# sensors.net
KiCad netlist of a schematic drawn in Altium Designer
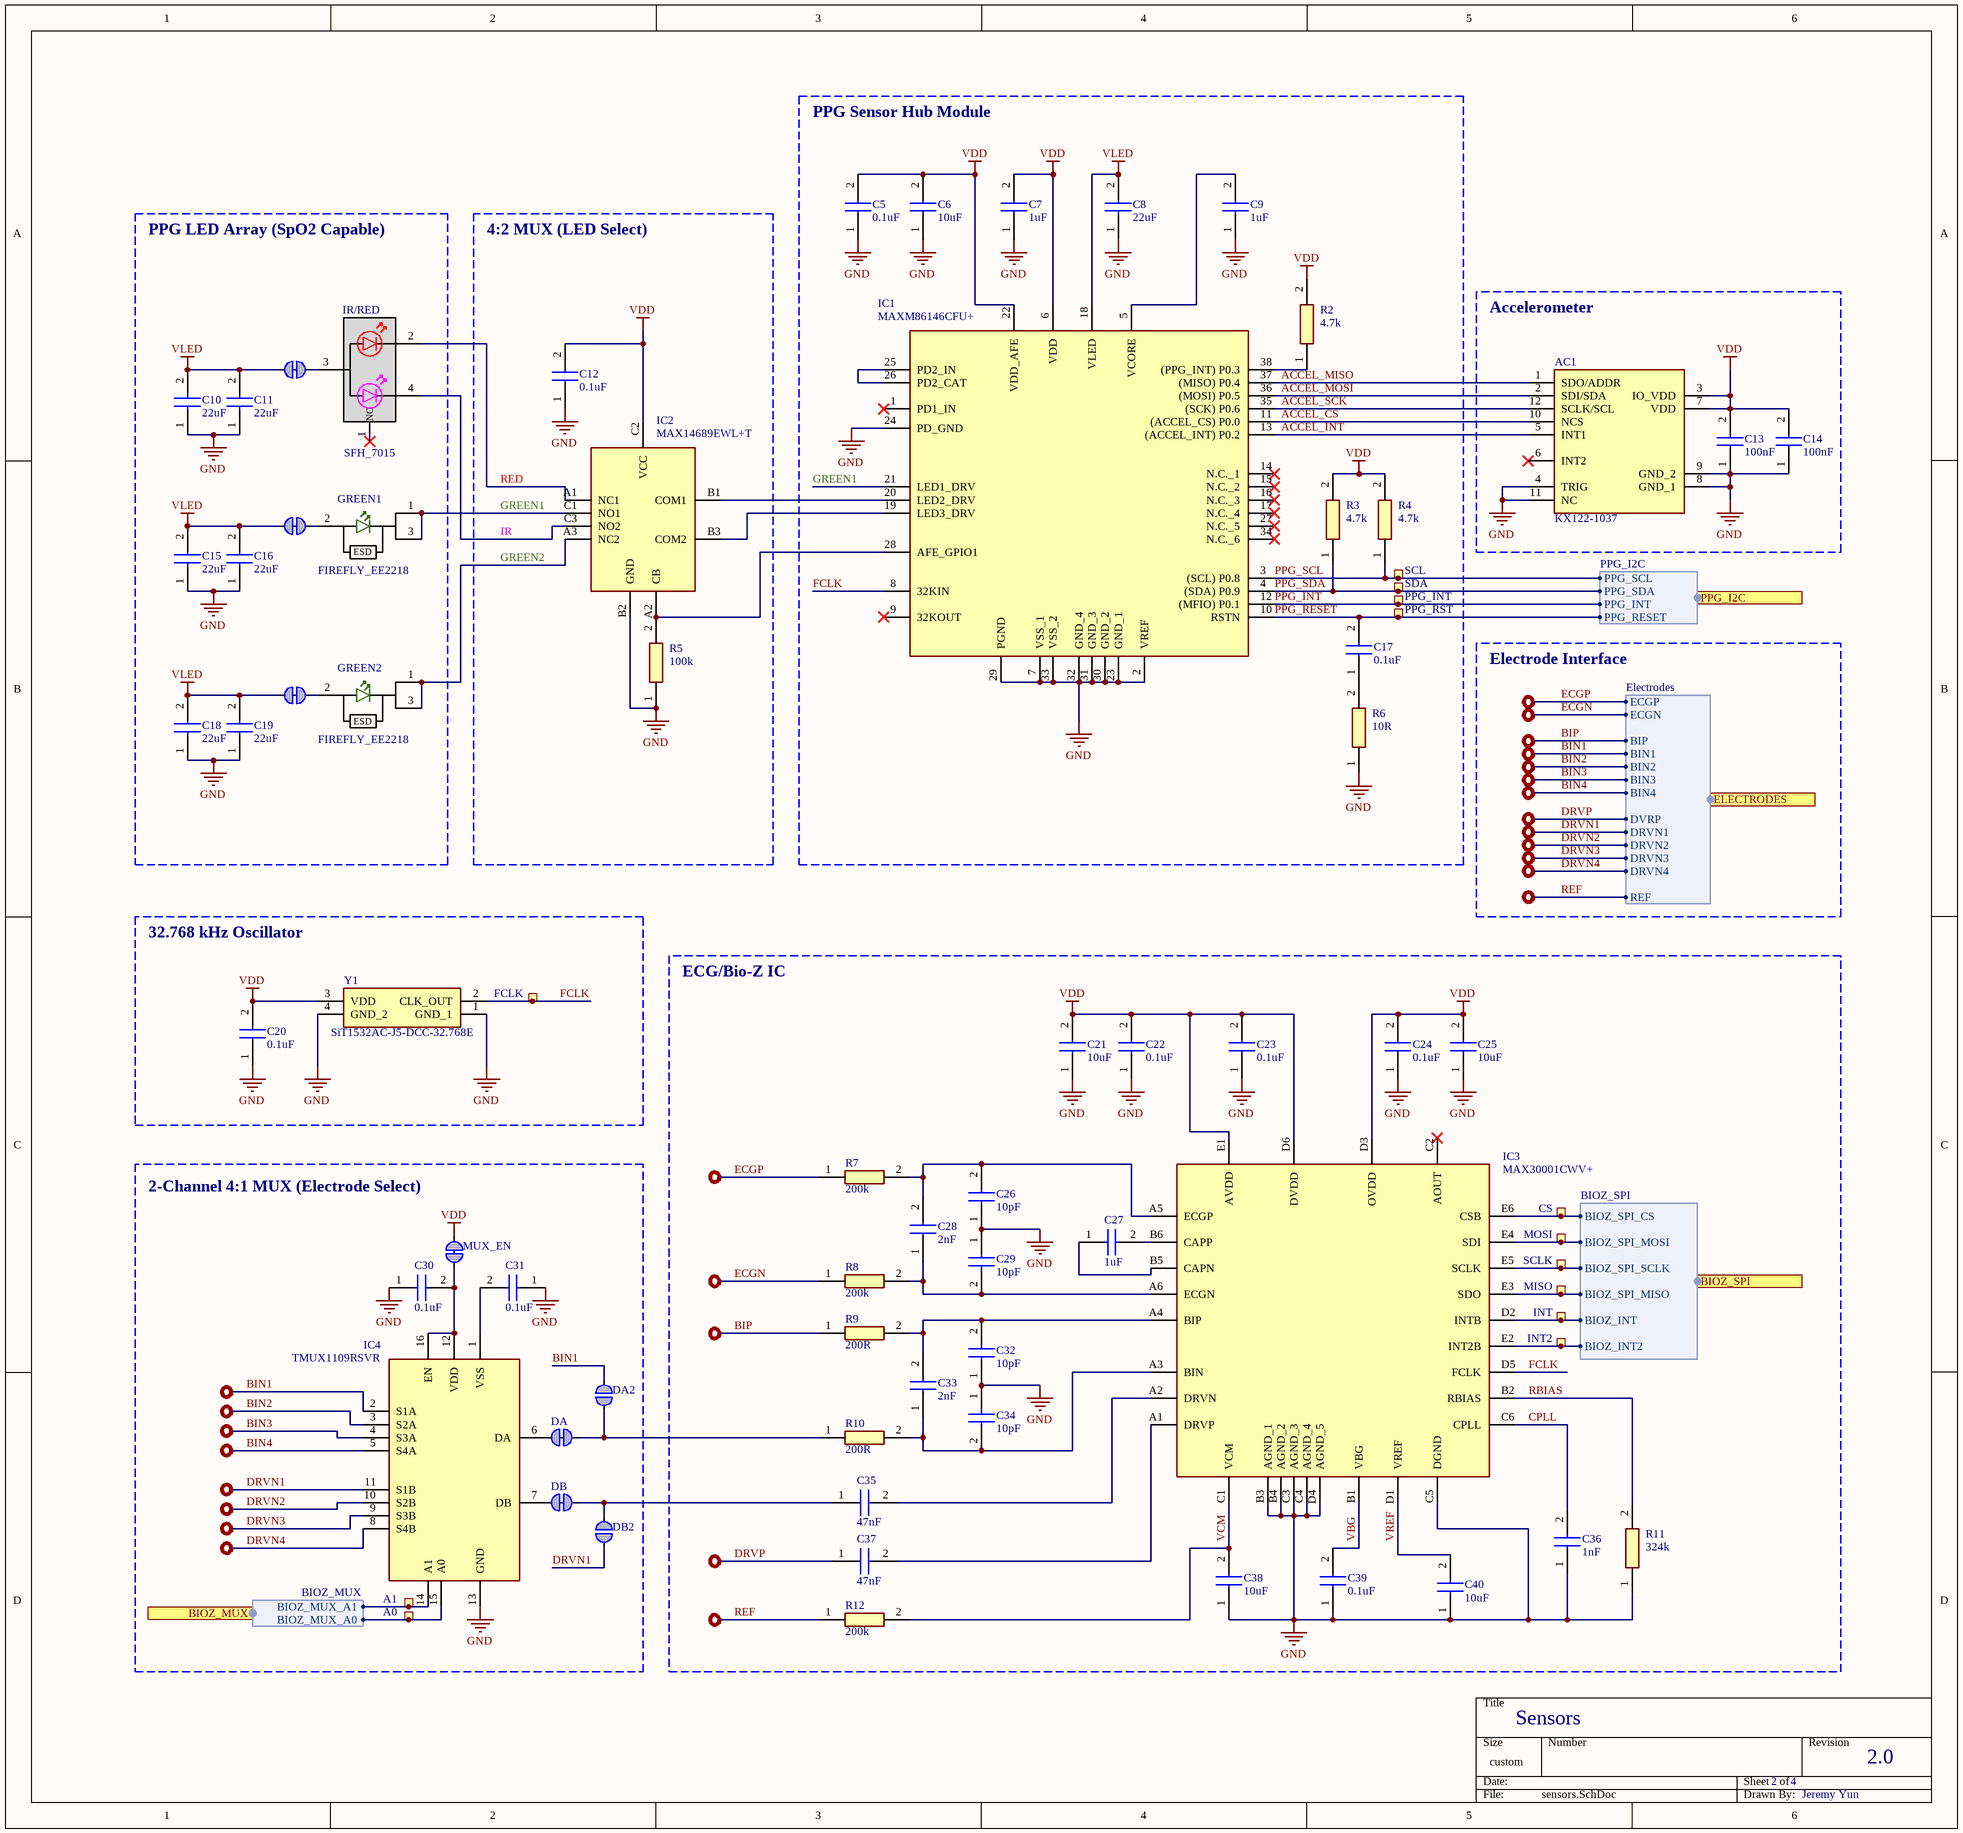
[diagram p0: sensors.SchDoc]

(export (version "E")
  (design (tool "Eeschema 10.0.6"))
  (components
    (comp (ref "A0")
      (value "Ø1.0mm,SMD")
      (footprint "TP_SMD_D1.0mm")
      (description "1.0mm circular SMD testpad")
      (fields
        (field (name "PART NUMBER") "TP_SMD_Ø1.0MM")
        (field (name "MANUFACTURER") "Nordic Semiconductor")
        (field (name "PUBLISHER") "Nordic Semiconductor")
        (field (name "AUTHOR") "rsk")
      )
      (libsource (lib "V2_wearable") (part "TP_SMD_Ø1.0MM"))
    )
    (comp (ref "A1")
      (value "Ø1.0mm,SMD")
      (footprint "TP_SMD_D1.0mm")
      (description "1.0mm circular SMD testpad")
      (fields
        (field (name "PART NUMBER") "TP_SMD_Ø1.0MM")
        (field (name "MANUFACTURER") "Nordic Semiconductor")
        (field (name "PUBLISHER") "Nordic Semiconductor")
        (field (name "AUTHOR") "rsk")
      )
      (libsource (lib "V2_wearable") (part "TP_SMD_Ø1.0MM"))
    )
    (comp (ref "AC1")
      (value "KX122-1037")
      (footprint "V2_wearable:KX1221037")
      (description "Accelerometer")
      (fields (field (name "MOUSER PART NUMBER") "912-KX122-1037"))
      (libsource (lib "V2_wearable") (part "KX122-1037"))
    )
    (comp (ref "C5")
      (value "0.1uF")
      (footprint "CAPC1005X55N")
      (description "Capacitor")
      (fields (field (name "MANUFACTURER_PART_NUMBER") "GRM155R71C104KA88D"))
      (libsource (lib "V2_wearable") (part "GRM155R71C104KA88D"))
    )
    (comp (ref "C6")
      (value "10uF")
      (footprint "V2_wearable:CAPC1005X55N")
      (description "Capacitor 10uF X5R Ceramic")
      (fields
        (field (name "MANUFACTURER_PART_NUMBER") "GRM155R60J106ME05D")
        (field (name "MOUSER PART NUMBER") "81-GRM155R60J106M05D")
      )
      (libsource (lib "*") (part "GRM155R60J106ME05D"))
    )
    (comp (ref "C7")
      (value "1uF")
      (footprint "CAPC1005X55N")
      (description "Capacitor")
      (fields
        (field (name "MANUFACTURER_PART_NUMBER") "CL05B104KP5NNNC")
        (field (name "MOUSER PART NUMBER") "187-CL05B104KP5NNNC")
      )
      (libsource (lib "V2_wearable") (part "CL05B104KP5NNNC"))
    )
    (comp (ref "C8")
      (value "22uF")
      (footprint "CAPC1005X55N")
      (description "Capacitor")
      (fields
        (field (name "MANUFACTURER_PART_NUMBER") "CL05B224KO5NNNC")
        (field (name "MOUSER PART NUMBER") "187-CL05B224KO5NNNC")
      )
      (libsource (lib "V2_wearable") (part "CL05B224KO5NNNC"))
    )
    (comp (ref "C9")
      (value "1uF")
      (footprint "CAPC1005X55N")
      (description "Capacitor")
      (fields
        (field (name "MANUFACTURER_PART_NUMBER") "CL05B104KP5NNNC")
        (field (name "MOUSER PART NUMBER") "187-CL05B104KP5NNNC")
      )
      (libsource (lib "V2_wearable") (part "CL05B104KP5NNNC"))
    )
    (comp (ref "C10")
      (value "22uF")
      (footprint "CAPC1005X55N")
      (description "Capacitor")
      (fields
        (field (name "MANUFACTURER_PART_NUMBER") "CL05B224KO5NNNC")
        (field (name "MOUSER PART NUMBER") "187-CL05B224KO5NNNC")
      )
      (libsource (lib "V2_wearable") (part "CL05B224KO5NNNC"))
    )
    (comp (ref "C11")
      (value "22uF")
      (footprint "CAPC1005X55N")
      (description "Capacitor")
      (fields
        (field (name "MANUFACTURER_PART_NUMBER") "CL05B224KO5NNNC")
        (field (name "MOUSER PART NUMBER") "187-CL05B224KO5NNNC")
      )
      (libsource (lib "V2_wearable") (part "CL05B224KO5NNNC"))
    )
    (comp (ref "C12")
      (value "0.1uF")
      (footprint "CAPC1005X55N")
      (description "Capacitor")
      (fields (field (name "MANUFACTURER_PART_NUMBER") "GRM155R71C104KA88D"))
      (libsource (lib "V2_wearable") (part "GRM155R71C104KA88D"))
    )
    (comp (ref "C13")
      (value "100nF")
      (footprint "CAPC1005X55N")
      (description "Capacitor")
      (fields
        (field (name "MANUFACTURER_PART_NUMBER") "CL05B104KP5VPNC")
        (field (name "MOUSER PART NUMBER") "187-CL05B104KP5VPNC")
      )
      (libsource (lib "V2_wearable") (part "CL05B104KP5VPNC"))
    )
    (comp (ref "C14")
      (value "100nF")
      (footprint "CAPC1005X55N")
      (description "Capacitor")
      (fields
        (field (name "MANUFACTURER_PART_NUMBER") "CL05B104KP5VPNC")
        (field (name "MOUSER PART NUMBER") "187-CL05B104KP5VPNC")
      )
      (libsource (lib "V2_wearable") (part "CL05B104KP5VPNC"))
    )
    (comp (ref "C15")
      (value "22uF")
      (footprint "CAPC1005X55N")
      (description "Capacitor")
      (fields
        (field (name "MANUFACTURER_PART_NUMBER") "CL05B224KO5NNNC")
        (field (name "MOUSER PART NUMBER") "187-CL05B224KO5NNNC")
      )
      (libsource (lib "V2_wearable") (part "CL05B224KO5NNNC"))
    )
    (comp (ref "C16")
      (value "22uF")
      (footprint "CAPC1005X55N")
      (description "Capacitor")
      (fields
        (field (name "MANUFACTURER_PART_NUMBER") "CL05B224KO5NNNC")
        (field (name "MOUSER PART NUMBER") "187-CL05B224KO5NNNC")
      )
      (libsource (lib "V2_wearable") (part "CL05B224KO5NNNC"))
    )
    (comp (ref "C17")
      (value "0.1uF")
      (footprint "CAPC1005X55N")
      (description "Capacitor")
      (fields (field (name "MANUFACTURER_PART_NUMBER") "GRM155R71C104KA88D"))
      (libsource (lib "V2_wearable") (part "GRM155R71C104KA88D"))
    )
    (comp (ref "C18")
      (value "22uF")
      (footprint "CAPC1005X55N")
      (description "Capacitor")
      (fields
        (field (name "MANUFACTURER_PART_NUMBER") "CL05B224KO5NNNC")
        (field (name "MOUSER PART NUMBER") "187-CL05B224KO5NNNC")
      )
      (libsource (lib "V2_wearable") (part "CL05B224KO5NNNC"))
    )
    (comp (ref "C19")
      (value "22uF")
      (footprint "CAPC1005X55N")
      (description "Capacitor")
      (fields
        (field (name "MANUFACTURER_PART_NUMBER") "CL05B224KO5NNNC")
        (field (name "MOUSER PART NUMBER") "187-CL05B224KO5NNNC")
      )
      (libsource (lib "V2_wearable") (part "CL05B224KO5NNNC"))
    )
    (comp (ref "C20")
      (value "0.1uF")
      (footprint "CAPC1005X55N")
      (description "Capacitor")
      (fields (field (name "MANUFACTURER_PART_NUMBER") "GRM155R71C104KA88D"))
      (libsource (lib "V2_wearable") (part "GRM155R71C104KA88D"))
    )
    (comp (ref "C21")
      (value "10uF")
      (footprint "V2_wearable:CAPC1005X55N")
      (description "Capacitor 10uF X5R Ceramic")
      (fields
        (field (name "MANUFACTURER_PART_NUMBER") "GRM155R60J106ME05D")
        (field (name "MOUSER PART NUMBER") "81-GRM155R60J106M05D")
      )
      (libsource (lib "*") (part "GRM155R60J106ME05D"))
    )
    (comp (ref "C22")
      (value "0.1uF")
      (footprint "CAPC1005X55N")
      (description "Capacitor")
      (fields (field (name "MANUFACTURER_PART_NUMBER") "GRM155R71C104KA88D"))
      (libsource (lib "V2_wearable") (part "GRM155R71C104KA88D"))
    )
    (comp (ref "C23")
      (value "0.1uF")
      (footprint "CAPC1005X55N")
      (description "Capacitor")
      (fields (field (name "MANUFACTURER_PART_NUMBER") "GRM155R71C104KA88D"))
      (libsource (lib "V2_wearable") (part "GRM155R71C104KA88D"))
    )
    (comp (ref "C24")
      (value "0.1uF")
      (footprint "CAPC1005X55N")
      (description "Capacitor")
      (fields (field (name "MANUFACTURER_PART_NUMBER") "GRM155R71C104KA88D"))
      (libsource (lib "V2_wearable") (part "GRM155R71C104KA88D"))
    )
    (comp (ref "C25")
      (value "10uF")
      (footprint "V2_wearable:CAPC1005X55N")
      (description "Capacitor 10uF X5R Ceramic")
      (fields
        (field (name "MANUFACTURER_PART_NUMBER") "GRM155R60J106ME05D")
        (field (name "MOUSER PART NUMBER") "81-GRM155R60J106M05D")
      )
      (libsource (lib "*") (part "GRM155R60J106ME05D"))
    )
    (comp (ref "C26")
      (value "10pF")
      (footprint "CAPC0603X33N")
      (description "Capacitor")
      (fields
        (field (name "MANUFACTURER_PART_NUMBER") "GRM0335C1E100JA01D")
        (field (name "MOUSER PART NUMBER") "81-GRM0335C1E100JA1D")
      )
      (libsource (lib "V2_wearable") (part "GRM0335C1E100JA01D"))
    )
    (comp (ref "C27")
      (value "1uF")
      (footprint "V2_wearable:CAPC1005X55N")
      (description "Capacitor")
      (fields
        (field (name "MANUFACTURER_PART_NUMBER") "CL05B104KP5NNNC")
        (field (name "MOUSER PART NUMBER") "187-CL05B104KP5NNNC")
      )
      (libsource (lib "V2_wearable") (part "CL05B104KP5NNNC"))
    )
    (comp (ref "C28")
      (value "2nF")
      (footprint "C0603")
      (description "Capacitor")
      (fields (field (name "MANUFACTURER_PART_NUMBER") "C0603C202G4HACAUTO"))
      (libsource (lib "V2_wearable") (part "C0603C202G4HACAUTO"))
    )
    (comp (ref "C29")
      (value "10pF")
      (footprint "CAPC0603X33N")
      (description "Capacitor")
      (fields
        (field (name "MANUFACTURER_PART_NUMBER") "GRM0335C1E100JA01D")
        (field (name "MOUSER PART NUMBER") "81-GRM0335C1E100JA1D")
      )
      (libsource (lib "V2_wearable") (part "GRM0335C1E100JA01D"))
    )
    (comp (ref "C30")
      (value "0.1uF")
      (footprint "CAPC1005X55N")
      (description "Capacitor")
      (fields (field (name "MANUFACTURER_PART_NUMBER") "GRM155R71C104KA88D"))
      (libsource (lib "V2_wearable") (part "GRM155R71C104KA88D"))
    )
    (comp (ref "C31")
      (value "0.1uF")
      (footprint "CAPC1005X55N")
      (description "Capacitor")
      (fields (field (name "MANUFACTURER_PART_NUMBER") "GRM155R71C104KA88D"))
      (libsource (lib "V2_wearable") (part "GRM155R71C104KA88D"))
    )
    (comp (ref "C32")
      (value "10pF")
      (footprint "CAPC0603X33N")
      (description "Capacitor")
      (fields
        (field (name "MANUFACTURER_PART_NUMBER") "GRM0335C1E100JA01D")
        (field (name "MOUSER PART NUMBER") "81-GRM0335C1E100JA1D")
      )
      (libsource (lib "V2_wearable") (part "GRM0335C1E100JA01D"))
    )
    (comp (ref "C33")
      (value "2nF")
      (footprint "C0603")
      (description "Capacitor")
      (fields (field (name "MANUFACTURER_PART_NUMBER") "C0603C202G4HACAUTO"))
      (libsource (lib "V2_wearable") (part "C0603C202G4HACAUTO"))
    )
    (comp (ref "C34")
      (value "10pF")
      (footprint "CAPC0603X33N")
      (description "Capacitor")
      (fields
        (field (name "MANUFACTURER_PART_NUMBER") "GRM0335C1E100JA01D")
        (field (name "MOUSER PART NUMBER") "81-GRM0335C1E100JA1D")
      )
      (libsource (lib "V2_wearable") (part "GRM0335C1E100JA01D"))
    )
    (comp (ref "C35")
      (value "47nF")
      (footprint "CAPC2012X140N")
      (description "Capacitor")
      (fields
        (field (name "MANUFACTURER_PART_NUMBER") "C0805C473K1RECAUTO7210")
        (field (name "MOUSER PART NUMBER") "80-C0805C473K1REAULR")
      )
      (libsource (lib "V2_wearable") (part "C0805C473K1RECAUTO7210"))
    )
    (comp (ref "C36")
      (value "1nF")
      (footprint "C0402")
      (description "Capacitor")
      (fields
        (field (name "MANUFACTURER_PART_NUMBER") "C0402C102J1GEC7411")
        (field (name "MOUSER PART NUMBER") "80-C0402C102J1GECLR")
      )
      (libsource (lib "V2_wearable") (part "C0402C102J1GEC7411"))
    )
    (comp (ref "C37")
      (value "47nF")
      (footprint "CAPC2012X140N")
      (description "Capacitor")
      (fields
        (field (name "MANUFACTURER_PART_NUMBER") "C0805C473K1RECAUTO7210")
        (field (name "MOUSER PART NUMBER") "80-C0805C473K1REAULR")
      )
      (libsource (lib "V2_wearable") (part "C0805C473K1RECAUTO7210"))
    )
    (comp (ref "C38")
      (value "10uF")
      (footprint "V2_wearable:CAPC1005X55N")
      (description "Capacitor 10uF X5R Ceramic")
      (fields
        (field (name "MANUFACTURER_PART_NUMBER") "GRM155R60J106ME05D")
        (field (name "MOUSER PART NUMBER") "81-GRM155R60J106M05D")
      )
      (libsource (lib "*") (part "GRM155R60J106ME05D"))
    )
    (comp (ref "C39")
      (value "0.1uF")
      (footprint "CAPC1005X55N")
      (description "Capacitor")
      (fields (field (name "MANUFACTURER_PART_NUMBER") "GRM155R71C104KA88D"))
      (libsource (lib "V2_wearable") (part "GRM155R71C104KA88D"))
    )
    (comp (ref "C40")
      (value "10uF")
      (footprint "V2_wearable:CAPC1005X55N")
      (description "Capacitor 10uF X5R Ceramic")
      (fields
        (field (name "MANUFACTURER_PART_NUMBER") "GRM155R60J106ME05D")
        (field (name "MOUSER PART NUMBER") "81-GRM155R60J106M05D")
      )
      (libsource (lib "*") (part "GRM155R60J106ME05D"))
    )
    (comp (ref "CS")
      (value "Ø1.0mm,SMD")
      (footprint "TP_SMD_D1.0mm")
      (description "1.0mm circular SMD testpad")
      (fields
        (field (name "PART NUMBER") "TP_SMD_Ø1.0MM")
        (field (name "MANUFACTURER") "Nordic Semiconductor")
        (field (name "PUBLISHER") "Nordic Semiconductor")
        (field (name "AUTHOR") "rsk")
      )
      (libsource (lib "V2_wearable") (part "TP_SMD_Ø1.0MM"))
    )
    (comp (ref "DA")
      (value "Solderbridge")
      (footprint "Solderbridge_Shorted")
      (description "Shorted Solderbridge")
      (fields
        (field (name "PART NUMBER") "Solderbridge Shorted")
        (field (name "MANUFACTURER") "N.A.")
        (field (name "PUBLISHER") "Nordic Semiconductor")
        (field (name "AUTHOR") "rsk")
      )
      (libsource (lib "V2_wearable") (part "Solderbridge Shorted"))
    )
    (comp (ref "DA2")
      (value "Solderbridge")
      (footprint "Solderbridge")
      (fields
        (field (name "MANUFACTURER") "N.A.")
        (field (name "PUBLISHER") "Nordic Semiconductor")
        (field (name "AUTHOR") "rsk")
      )
      (libsource (lib "V2_wearable") (part "Solderbridge"))
    )
    (comp (ref "DB")
      (value "Solderbridge")
      (footprint "Solderbridge_Shorted")
      (description "Shorted Solderbridge")
      (fields
        (field (name "PART NUMBER") "Solderbridge Shorted")
        (field (name "MANUFACTURER") "N.A.")
        (field (name "PUBLISHER") "Nordic Semiconductor")
        (field (name "AUTHOR") "rsk")
      )
      (libsource (lib "V2_wearable") (part "Solderbridge Shorted"))
    )
    (comp (ref "DB2")
      (value "Solderbridge")
      (footprint "Solderbridge")
      (fields
        (field (name "MANUFACTURER") "N.A.")
        (field (name "PUBLISHER") "Nordic Semiconductor")
        (field (name "AUTHOR") "rsk")
      )
      (libsource (lib "V2_wearable") (part "Solderbridge"))
    )
    (comp (ref "FCLK")
      (value "Ø1.0mm,SMD")
      (footprint "TP_SMD_D1.0mm")
      (description "1.0mm circular SMD testpad")
      (fields
        (field (name "PART NUMBER") "TP_SMD_Ø1.0MM")
        (field (name "MANUFACTURER") "Nordic Semiconductor")
        (field (name "PUBLISHER") "Nordic Semiconductor")
        (field (name "AUTHOR") "rsk")
      )
      (libsource (lib "V2_wearable") (part "TP_SMD_Ø1.0MM"))
    )
    (comp (ref "GR1")
      (value "Solderbridge")
      (footprint "Solderbridge_Shorted")
      (description "Shorted Solderbridge")
      (fields
        (field (name "PART NUMBER") "Solderbridge Shorted")
        (field (name "MANUFACTURER") "N.A.")
        (field (name "PUBLISHER") "Nordic Semiconductor")
        (field (name "AUTHOR") "rsk")
      )
      (libsource (lib "V2_wearable") (part "Solderbridge Shorted"))
    )
    (comp (ref "GR2")
      (value "Solderbridge")
      (footprint "Solderbridge_Shorted")
      (description "Shorted Solderbridge")
      (fields
        (field (name "PART NUMBER") "Solderbridge Shorted")
        (field (name "MANUFACTURER") "N.A.")
        (field (name "PUBLISHER") "Nordic Semiconductor")
        (field (name "AUTHOR") "rsk")
      )
      (libsource (lib "V2_wearable") (part "Solderbridge Shorted"))
    )
    (comp (ref "GREEN1")
      (value "FIREFLY_EE2218")
      (footprint "V2_wearable:CTDBLP31126C5D56J6U620R18")
      (description "LED")
      (fields
        (field (name "MANUFACTURER_PART_NUMBER") "CT DBLP31.12-6C5D-56-J6U6-20-R18")
        (field (name "MOUSER PART NUMBER") "720-CTDBLP31A6091")
      )
      (libsource (lib "V2_wearable") (part "CT_DBLP31.12-6C5D-56-J6U6-20-R18"))
    )
    (comp (ref "GREEN2")
      (value "FIREFLY_EE2218")
      (footprint "V2_wearable:CTDBLP31126C5D56J6U620R18")
      (description "LED")
      (fields
        (field (name "MANUFACTURER_PART_NUMBER") "CT DBLP31.12-6C5D-56-J6U6-20-R18")
        (field (name "MOUSER PART NUMBER") "720-CTDBLP31A6091")
      )
      (libsource (lib "V2_wearable") (part "CT_DBLP31.12-6C5D-56-J6U6-20-R18"))
    )
    (comp (ref "IC1")
      (value "MAXM86146CFU+")
      (footprint "V2_wearable:MAXM86146CFU")
      (description "Integrated Circuit")
      (fields (field (name "MOUSER PART NUMBER") "700-MAXM86146CFU+"))
      (libsource (lib "V2_wearable") (part "MAXM86146CFU+"))
    )
    (comp (ref "IC2")
      (value "MAX14689EWL+T")
      (footprint "V2_wearable:BGA9C40P3X3_124X124X69")
      (description "Integrated Circuit")
      (fields (field (name "MOUSER PART NUMBER") "700-MAX14689EWL+T"))
      (libsource (lib "V2_wearable") (part "MAX14689EWL+T"))
    )
    (comp (ref "IC3")
      (value "MAX30001CWV+")
      (footprint "V2_wearable:BGA30C50P6X5_293X274X69")
      (description "Integrated Circuit")
      (fields (field (name "MOUSER PART NUMBER") "700-MAX30001CWV+"))
      (libsource (lib "V2_wearable") (part "MAX30001CWV+"))
    )
    (comp (ref "IC4")
      (value "TMUX1109RSVR")
      (footprint "V2_wearable:TMUX1109RSVR")
      (description "Integrated Circuit")
      (libsource (lib "V2_wearable") (part "TMUX1109RSVR"))
    )
    (comp (ref "INT")
      (value "Ø1.0mm,SMD")
      (footprint "TP_SMD_D1.0mm")
      (description "1.0mm circular SMD testpad")
      (fields
        (field (name "PART NUMBER") "TP_SMD_Ø1.0MM")
        (field (name "MANUFACTURER") "Nordic Semiconductor")
        (field (name "PUBLISHER") "Nordic Semiconductor")
        (field (name "AUTHOR") "rsk")
      )
      (libsource (lib "V2_wearable") (part "TP_SMD_Ø1.0MM"))
    )
    (comp (ref "INT2")
      (value "Ø1.0mm,SMD")
      (footprint "TP_SMD_D1.0mm")
      (description "1.0mm circular SMD testpad")
      (fields
        (field (name "PART NUMBER") "TP_SMD_Ø1.0MM")
        (field (name "MANUFACTURER") "Nordic Semiconductor")
        (field (name "PUBLISHER") "Nordic Semiconductor")
        (field (name "AUTHOR") "rsk")
      )
      (libsource (lib "V2_wearable") (part "TP_SMD_Ø1.0MM"))
    )
    (comp (ref "IR/RED")
      (value "SFH_7015")
      (footprint "V2_wearable:SFH7015")
      (description "LED")
      (fields
        (field (name "MANUFACTURER_PART_NUMBER") "SFH 7015")
        (field (name "MOUSER PART NUMBER") "720-SFH7015")
      )
      (libsource (lib "V2_wearable") (part "SFH_7015"))
    )
    (comp (ref "MISO")
      (value "Ø1.0mm,SMD")
      (footprint "TP_SMD_D1.0mm")
      (description "1.0mm circular SMD testpad")
      (fields
        (field (name "PART NUMBER") "TP_SMD_Ø1.0MM")
        (field (name "MANUFACTURER") "Nordic Semiconductor")
        (field (name "PUBLISHER") "Nordic Semiconductor")
        (field (name "AUTHOR") "rsk")
      )
      (libsource (lib "V2_wearable") (part "TP_SMD_Ø1.0MM"))
    )
    (comp (ref "MOSI")
      (value "Ø1.0mm,SMD")
      (footprint "TP_SMD_D1.0mm")
      (description "1.0mm circular SMD testpad")
      (fields
        (field (name "PART NUMBER") "TP_SMD_Ø1.0MM")
        (field (name "MANUFACTURER") "Nordic Semiconductor")
        (field (name "PUBLISHER") "Nordic Semiconductor")
        (field (name "AUTHOR") "rsk")
      )
      (libsource (lib "V2_wearable") (part "TP_SMD_Ø1.0MM"))
    )
    (comp (ref "MUX_EN")
      (value "Solderbridge")
      (footprint "Solderbridge_Shorted")
      (description "Shorted Solderbridge")
      (fields
        (field (name "PART NUMBER") "Solderbridge Shorted")
        (field (name "MANUFACTURER") "N.A.")
        (field (name "PUBLISHER") "Nordic Semiconductor")
        (field (name "AUTHOR") "rsk")
      )
      (libsource (lib "V2_wearable") (part "Solderbridge Shorted"))
    )
    (comp (ref "PPG_INT")
      (value "Ø1.0mm,SMD")
      (footprint "TP_SMD_D1.0mm")
      (description "1.0mm circular SMD testpad")
      (fields
        (field (name "PART NUMBER") "TP_SMD_Ø1.0MM")
        (field (name "MANUFACTURER") "Nordic Semiconductor")
        (field (name "PUBLISHER") "Nordic Semiconductor")
        (field (name "AUTHOR") "rsk")
      )
      (libsource (lib "V2_wearable") (part "TP_SMD_Ø1.0MM"))
    )
    (comp (ref "PPG_RST")
      (value "Ø1.0mm,SMD")
      (footprint "TP_SMD_D1.0mm")
      (description "1.0mm circular SMD testpad")
      (fields
        (field (name "PART NUMBER") "TP_SMD_Ø1.0MM")
        (field (name "MANUFACTURER") "Nordic Semiconductor")
        (field (name "PUBLISHER") "Nordic Semiconductor")
        (field (name "AUTHOR") "rsk")
      )
      (libsource (lib "V2_wearable") (part "TP_SMD_Ø1.0MM"))
    )
    (comp (ref "R2")
      (value "4.7k")
      (footprint "RESC1005X40N")
      (description "Resistor")
      (fields
        (field (name "MANUFACTURER_PART_NUMBER") "RC0402FR-074K7L")
        (field (name "MOUSER PART NUMBER") "603-RC0402FR-074K7L")
      )
      (libsource (lib "V2_wearable") (part "RC0402FR-074K7L"))
    )
    (comp (ref "R3")
      (value "4.7k")
      (footprint "RESC1005X40N")
      (description "Resistor")
      (fields
        (field (name "MANUFACTURER_PART_NUMBER") "RC0402FR-074K7L")
        (field (name "MOUSER PART NUMBER") "603-RC0402FR-074K7L")
      )
      (libsource (lib "V2_wearable") (part "RC0402FR-074K7L"))
    )
    (comp (ref "R4")
      (value "4.7k")
      (footprint "RESC1005X40N")
      (description "Resistor")
      (fields
        (field (name "MANUFACTURER_PART_NUMBER") "RC0402FR-074K7L")
        (field (name "MOUSER PART NUMBER") "603-RC0402FR-074K7L")
      )
      (libsource (lib "V2_wearable") (part "RC0402FR-074K7L"))
    )
    (comp (ref "R5")
      (value "100k")
      (footprint "RESC1005X40N")
      (description "Resistor")
      (fields
        (field (name "MANUFACTURER_PART_NUMBER") "RC0402FR-07100KL")
        (field (name "MOUSER PART NUMBER") "603-RC0402FR-07100KL")
      )
      (libsource (lib "V2_wearable") (part "RC0402FR-07100KL"))
    )
    (comp (ref "R6")
      (value "10R")
      (footprint "RESC1005X40N")
      (description "Resistor")
      (fields
        (field (name "MANUFACTURER_PART_NUMBER") "RC0402FR-0710RL")
        (field (name "MOUSER PART NUMBER") "603-RC0402FR-0710RL")
      )
      (libsource (lib "V2_wearable") (part "RC0402FR-0710RL"))
    )
    (comp (ref "R7")
      (value "200k")
      (footprint "V2_wearable:ERJ2RKD1004X")
      (description "Resistor")
      (fields
        (field (name "MANUFACTURER_PART_NUMBER") "ERJ-2RKF2003X")
        (field (name "MOUSER PART NUMBER") "667-ERJ-2RKF2003X")
      )
      (libsource (lib "*") (part "ERJ-2RKF2003X"))
    )
    (comp (ref "R8")
      (value "200k")
      (footprint "V2_wearable:ERJ2RKD1004X")
      (description "Resistor")
      (fields
        (field (name "MANUFACTURER_PART_NUMBER") "ERJ-2RKF2003X")
        (field (name "MOUSER PART NUMBER") "667-ERJ-2RKF2003X")
      )
      (libsource (lib "*") (part "ERJ-2RKF2003X"))
    )
    (comp (ref "R9")
      (value "200R")
      (footprint "ERJ2RKD1004X")
      (description "Resistor")
      (fields
        (field (name "MANUFACTURER_PART_NUMBER") "ERJ-2RKF2000X")
        (field (name "MOUSER PART NUMBER") "667-ERJ-2RKF2000X")
      )
      (libsource (lib "V2_wearable") (part "ERJ-2RKF2000X"))
    )
    (comp (ref "R10")
      (value "200R")
      (footprint "ERJ2RKD1004X")
      (description "Resistor")
      (fields
        (field (name "MANUFACTURER_PART_NUMBER") "ERJ-2RKF2000X")
        (field (name "MOUSER PART NUMBER") "667-ERJ-2RKF2000X")
      )
      (libsource (lib "V2_wearable") (part "ERJ-2RKF2000X"))
    )
    (comp (ref "R11")
      (value "324k")
      (footprint "V2_wearable:RESC1608X55N")
      (description "Resistor")
      (fields
        (field (name "MANUFACTURER_PART_NUMBER") "RN73C1J324KBTDF")
        (field (name "MOUSER PART NUMBER") "279-RN73C1J324KBTDF")
      )
      (libsource (lib "V2_wearable") (part "RN73C1J324KBTDF"))
    )
    (comp (ref "R12")
      (value "200k")
      (footprint "ERJ2RKD1004X")
      (description "Resistor")
      (fields
        (field (name "MANUFACTURER_PART_NUMBER") "ERJ-2RKF2003X")
        (field (name "MOUSER PART NUMBER") "667-ERJ-2RKF2003X")
      )
      (libsource (lib "V2_wearable") (part "ERJ-2RKF2003X"))
    )
    (comp (ref "RED/IR")
      (value "Solderbridge")
      (footprint "Solderbridge_Shorted")
      (description "Shorted Solderbridge")
      (fields
        (field (name "PART NUMBER") "Solderbridge Shorted")
        (field (name "MANUFACTURER") "N.A.")
        (field (name "PUBLISHER") "Nordic Semiconductor")
        (field (name "AUTHOR") "rsk")
      )
      (libsource (lib "V2_wearable") (part "Solderbridge Shorted"))
    )
    (comp (ref "SCL")
      (value "Ø1.0mm,SMD")
      (footprint "TP_SMD_D1.0mm")
      (description "1.0mm circular SMD testpad")
      (fields
        (field (name "PART NUMBER") "TP_SMD_Ø1.0MM")
        (field (name "MANUFACTURER") "Nordic Semiconductor")
        (field (name "PUBLISHER") "Nordic Semiconductor")
        (field (name "AUTHOR") "rsk")
      )
      (libsource (lib "V2_wearable") (part "TP_SMD_Ø1.0MM"))
    )
    (comp (ref "SCLK")
      (value "Ø1.0mm,SMD")
      (footprint "TP_SMD_D1.0mm")
      (description "1.0mm circular SMD testpad")
      (fields
        (field (name "PART NUMBER") "TP_SMD_Ø1.0MM")
        (field (name "MANUFACTURER") "Nordic Semiconductor")
        (field (name "PUBLISHER") "Nordic Semiconductor")
        (field (name "AUTHOR") "rsk")
      )
      (libsource (lib "V2_wearable") (part "TP_SMD_Ø1.0MM"))
    )
    (comp (ref "SDA")
      (value "Ø1.0mm,SMD")
      (footprint "TP_SMD_D1.0mm")
      (description "1.0mm circular SMD testpad")
      (fields
        (field (name "PART NUMBER") "TP_SMD_Ø1.0MM")
        (field (name "MANUFACTURER") "Nordic Semiconductor")
        (field (name "PUBLISHER") "Nordic Semiconductor")
        (field (name "AUTHOR") "rsk")
      )
      (libsource (lib "V2_wearable") (part "TP_SMD_Ø1.0MM"))
    )
    (comp (ref "Y1")
      (value "SiT1532AC-J5-DCC-32.768E")
      (footprint "SiT1532ACJ5DCC32768E")
      (description "Crystal or Oscillator")
      (fields
        (field (name "MOUSER PART NUMBER") "788-1532ACJ5DCC32.7E")
        (field (name "ARROW PART NUMBER") "SIT1532AC-J5-DCC-32.768E")
      )
      (libsource (lib "V2_wearable") (part "SiT1532AC-J5-DCC-32.768E"))
    )
  )
  (nets
    (net (code "5") (name "/ACCEL_CS") (class "Default")
      (node (ref "AC1") (pin "10") (pinfunction "NCS_10") (pintype "passive"))
      (node (ref "IC1") (pin "11") (pinfunction "(ACCEL_CS)_P0.0_11") (pintype "passive"))
    )
    (net (code "6") (name "/ACCEL_INT") (class "Default")
      (node (ref "AC1") (pin "5") (pinfunction "INT1_5") (pintype "passive"))
      (node (ref "IC1") (pin "13") (pinfunction "(ACCEL_INT)_P0.2_13") (pintype "passive"))
    )
    (net (code "7") (name "/ACCEL_MISO") (class "Default")
      (node (ref "AC1") (pin "1") (pinfunction "SDO/ADDR_1") (pintype "passive"))
      (node (ref "IC1") (pin "37") (pinfunction "(MISO)_P0.4_37") (pintype "passive"))
    )
    (net (code "8") (name "/ACCEL_MOSI") (class "Default")
      (node (ref "AC1") (pin "2") (pinfunction "SDI/SDA_2") (pintype "passive"))
      (node (ref "IC1") (pin "36") (pinfunction "(MOSI)_P0.5_36") (pintype "passive"))
    )
    (net (code "9") (name "/ACCEL_SCK") (class "Default")
      (node (ref "AC1") (pin "12") (pinfunction "SCLK/SCL_12") (pintype "passive"))
      (node (ref "IC1") (pin "35") (pinfunction "(SCK)_P0.6_35") (pintype "passive"))
    )
    (net (code "10") (name "/BIN1") (class "Default")
      (node (ref "DA2") (pin "1") (pinfunction "0_1") (pintype "passive"))
      (node (ref "IC4") (pin "2") (pinfunction "S1A_2") (pintype "passive"))
    )
    (net (code "11") (name "/BIN2") (class "Default")
      (node (ref "IC4") (pin "3") (pinfunction "S2A_3") (pintype "passive"))
    )
    (net (code "12") (name "/BIN3") (class "Default")
      (node (ref "IC4") (pin "4") (pinfunction "S3A_4") (pintype "passive"))
    )
    (net (code "13") (name "/BIN4") (class "Default")
      (node (ref "IC4") (pin "5") (pinfunction "S4A_5") (pintype "passive"))
    )
    (net (code "14") (name "/BIP") (class "Default")
      (node (ref "R9") (pin "1") (pinfunction "1_1") (pintype "passive"))
    )
    (net (code "15") (name "/CPLL") (class "Default")
      (node (ref "C36") (pin "2") (pinfunction "2_2") (pintype "passive"))
      (node (ref "IC3") (pin "C6") (pinfunction "CPLL_C6") (pintype "passive"))
    )
    (net (code "16") (name "/DRVN1") (class "Default")
      (node (ref "DB2") (pin "2") (pinfunction "1_2") (pintype "passive"))
      (node (ref "IC4") (pin "11") (pinfunction "S1B_11") (pintype "passive"))
    )
    (net (code "17") (name "/DRVN2") (class "Default")
      (node (ref "IC4") (pin "10") (pinfunction "S2B_10") (pintype "passive"))
    )
    (net (code "18") (name "/DRVN3") (class "Default")
      (node (ref "IC4") (pin "9") (pinfunction "S3B_9") (pintype "passive"))
    )
    (net (code "19") (name "/DRVN4") (class "Default")
      (node (ref "IC4") (pin "8") (pinfunction "S4B_8") (pintype "passive"))
    )
    (net (code "20") (name "/DRVP") (class "Default")
      (node (ref "C37") (pin "1") (pinfunction "1_1") (pintype "passive"))
    )
    (net (code "21") (name "/ECGN") (class "Default")
      (node (ref "R8") (pin "1") (pinfunction "1_1") (pintype "passive"))
    )
    (net (code "22") (name "/ECGP") (class "Default")
      (node (ref "R7") (pin "1") (pinfunction "1_1") (pintype "passive"))
    )
    (net (code "23") (name "/FCLK") (class "Default")
      (node (ref "FCLK") (pin "1") (pinfunction "1_1") (pintype "passive"))
      (node (ref "IC1") (pin "8") (pinfunction "32KIN_8") (pintype "passive"))
      (node (ref "IC3") (pin "D5") (pinfunction "FCLK_D5") (pintype "passive"))
      (node (ref "Y1") (pin "2") (pinfunction "CLK_OUT_2") (pintype "passive"))
    )
    (net (code "24") (name "/GREEN1") (class "Default")
      (node (ref "GREEN1") (pin "1") (pinfunction "K_1_1") (pintype "passive"))
      (node (ref "GREEN1") (pin "3") (pinfunction "K_2_3") (pintype "passive"))
      (node (ref "IC1") (pin "21") (pinfunction "LED1_DRV_21") (pintype "passive"))
      (node (ref "IC2") (pin "C1") (pinfunction "NO1_C1") (pintype "passive"))
    )
    (net (code "25") (name "/GREEN2") (class "Default")
      (node (ref "GREEN2") (pin "1") (pinfunction "K_1_1") (pintype "passive"))
      (node (ref "GREEN2") (pin "3") (pinfunction "K_2_3") (pintype "passive"))
      (node (ref "IC2") (pin "A3") (pinfunction "NC2_A3") (pintype "passive"))
    )
    (net (code "26") (name "/IR") (class "Default")
      (node (ref "IC2") (pin "C3") (pinfunction "NO2_C3") (pintype "passive"))
      (node (ref "IR/RED") (pin "4") (pinfunction "CATHODE_EMITTER_2_(940_NM)_4") (pintype "passive"))
    )
    (net (code "27") (name "/PPG_INT") (class "Default")
      (node (ref "IC1") (pin "12") (pinfunction "(MFIO)_P0.1_12") (pintype "passive"))
      (node (ref "PPG_INT") (pin "1") (pinfunction "1_1") (pintype "passive"))
    )
    (net (code "28") (name "/PPG_RESET") (class "Default")
      (node (ref "C17") (pin "2") (pinfunction "2_2") (pintype "passive"))
      (node (ref "IC1") (pin "10") (pinfunction "RSTN_10") (pintype "passive"))
      (node (ref "PPG_RST") (pin "1") (pinfunction "1_1") (pintype "passive"))
    )
    (net (code "29") (name "/PPG_SCL") (class "Default")
      (node (ref "IC1") (pin "3") (pinfunction "(SCL)_P0.8_3") (pintype "passive"))
      (node (ref "R4") (pin "1") (pinfunction "1_1") (pintype "passive"))
      (node (ref "SCL") (pin "1") (pinfunction "1_1") (pintype "passive"))
    )
    (net (code "30") (name "/PPG_SDA") (class "Default")
      (node (ref "IC1") (pin "4") (pinfunction "(SDA)_P0.9_4") (pintype "passive"))
      (node (ref "R3") (pin "1") (pinfunction "1_1") (pintype "passive"))
      (node (ref "SDA") (pin "1") (pinfunction "1_1") (pintype "passive"))
    )
    (net (code "31") (name "/RBIAS") (class "Default")
      (node (ref "IC3") (pin "B2") (pinfunction "RBIAS_B2") (pintype "passive"))
      (node (ref "R11") (pin "2") (pinfunction "2_2") (pintype "passive"))
    )
    (net (code "32") (name "/RED") (class "Default")
      (node (ref "IC2") (pin "A1") (pinfunction "NC1_A1") (pintype "passive"))
      (node (ref "IR/RED") (pin "2") (pinfunction "CATHODE_EMITTER_1_(655_NM)_2") (pintype "passive"))
    )
    (net (code "33") (name "/REF") (class "Default")
      (node (ref "R12") (pin "1") (pinfunction "1_1") (pintype "passive"))
    )
    (net (code "34") (name "/VBG") (class "Default")
      (node (ref "C39") (pin "2") (pinfunction "2_2") (pintype "passive"))
      (node (ref "IC3") (pin "B1") (pinfunction "VBG_B1") (pintype "passive"))
    )
    (net (code "35") (name "/VCM") (class "Default")
      (node (ref "C38") (pin "2") (pinfunction "2_2") (pintype "passive"))
      (node (ref "IC3") (pin "C1") (pinfunction "VCM_C1") (pintype "passive"))
      (node (ref "R12") (pin "2") (pinfunction "2_2") (pintype "passive"))
    )
    (net (code "36") (name "/VREF") (class "Default")
      (node (ref "C40") (pin "2") (pinfunction "2_2") (pintype "passive"))
      (node (ref "IC3") (pin "D1") (pinfunction "VREF_D1") (pintype "passive"))
    )
    (net (code "41") (name "GND") (class "Default")
      (node (ref "AC1") (pin "11") (pinfunction "NC_11") (pintype "passive"))
      (node (ref "AC1") (pin "4") (pinfunction "TRIG_4") (pintype "passive"))
      (node (ref "AC1") (pin "8") (pinfunction "GND_1_8") (pintype "passive"))
      (node (ref "AC1") (pin "9") (pinfunction "GND_2_9") (pintype "passive"))
      (node (ref "C10") (pin "1") (pinfunction "1_1") (pintype "passive"))
      (node (ref "C11") (pin "1") (pinfunction "1_1") (pintype "passive"))
      (node (ref "C12") (pin "1") (pinfunction "1_1") (pintype "passive"))
      (node (ref "C13") (pin "1") (pinfunction "1_1") (pintype "passive"))
      (node (ref "C14") (pin "1") (pinfunction "1_1") (pintype "passive"))
      (node (ref "C15") (pin "1") (pinfunction "1_1") (pintype "passive"))
      (node (ref "C16") (pin "1") (pinfunction "1_1") (pintype "passive"))
      (node (ref "C18") (pin "1") (pinfunction "1_1") (pintype "passive"))
      (node (ref "C19") (pin "1") (pinfunction "1_1") (pintype "passive"))
      (node (ref "C20") (pin "1") (pinfunction "1_1") (pintype "passive"))
      (node (ref "C21") (pin "1") (pinfunction "1_1") (pintype "passive"))
      (node (ref "C22") (pin "1") (pinfunction "1_1") (pintype "passive"))
      (node (ref "C23") (pin "1") (pinfunction "1_1") (pintype "passive"))
      (node (ref "C24") (pin "1") (pinfunction "1_1") (pintype "passive"))
      (node (ref "C25") (pin "1") (pinfunction "1_1") (pintype "passive"))
      (node (ref "C26") (pin "1") (pinfunction "1_1") (pintype "passive"))
      (node (ref "C29") (pin "1") (pinfunction "1_1") (pintype "passive"))
      (node (ref "C30") (pin "1") (pinfunction "1_1") (pintype "passive"))
      (node (ref "C31") (pin "1") (pinfunction "1_1") (pintype "passive"))
      (node (ref "C32") (pin "1") (pinfunction "1_1") (pintype "passive"))
      (node (ref "C34") (pin "1") (pinfunction "1_1") (pintype "passive"))
      (node (ref "C36") (pin "1") (pinfunction "1_1") (pintype "passive"))
      (node (ref "C38") (pin "1") (pinfunction "1_1") (pintype "passive"))
      (node (ref "C39") (pin "1") (pinfunction "1_1") (pintype "passive"))
      (node (ref "C40") (pin "1") (pinfunction "1_1") (pintype "passive"))
      (node (ref "C5") (pin "1") (pinfunction "1_1") (pintype "passive"))
      (node (ref "C6") (pin "1") (pinfunction "1_1") (pintype "passive"))
      (node (ref "C7") (pin "1") (pinfunction "1_1") (pintype "passive"))
      (node (ref "C8") (pin "1") (pinfunction "1_1") (pintype "passive"))
      (node (ref "C9") (pin "1") (pinfunction "1_1") (pintype "passive"))
      (node (ref "IC1") (pin "2") (pinfunction "VREF_2") (pintype "passive"))
      (node (ref "IC1") (pin "23") (pinfunction "GND_1_23") (pintype "passive"))
      (node (ref "IC1") (pin "24") (pinfunction "PD_GND_24") (pintype "passive"))
      (node (ref "IC1") (pin "29") (pinfunction "PGND_29") (pintype "passive"))
      (node (ref "IC1") (pin "30") (pinfunction "GND_2_30") (pintype "passive"))
      (node (ref "IC1") (pin "31") (pinfunction "GND_3_31") (pintype "passive"))
      (node (ref "IC1") (pin "32") (pinfunction "GND_4_32") (pintype "passive"))
      (node (ref "IC1") (pin "33") (pinfunction "VSS_2_33") (pintype "passive"))
      (node (ref "IC1") (pin "7") (pinfunction "VSS_1_7") (pintype "passive"))
      (node (ref "IC2") (pin "B2") (pinfunction "GND_B2") (pintype "passive"))
      (node (ref "IC3") (pin "B3") (pinfunction "AGND_1_B3") (pintype "passive"))
      (node (ref "IC3") (pin "B4") (pinfunction "AGND_2_B4") (pintype "passive"))
      (node (ref "IC3") (pin "C3") (pinfunction "AGND_3_C3") (pintype "passive"))
      (node (ref "IC3") (pin "C4") (pinfunction "AGND_4_C4") (pintype "passive"))
      (node (ref "IC3") (pin "C5") (pinfunction "DGND_C5") (pintype "passive"))
      (node (ref "IC3") (pin "D4") (pinfunction "AGND_5_D4") (pintype "passive"))
      (node (ref "IC4") (pin "13") (pinfunction "GND_13") (pintype "passive"))
      (node (ref "R11") (pin "1") (pinfunction "1_1") (pintype "passive"))
      (node (ref "R5") (pin "1") (pinfunction "1_1") (pintype "passive"))
      (node (ref "R6") (pin "1") (pinfunction "1_1") (pintype "passive"))
      (node (ref "Y1") (pin "1") (pinfunction "GND_1_1") (pintype "passive"))
      (node (ref "Y1") (pin "4") (pinfunction "GND_2_4") (pintype "passive"))
    )
    (net (code "42") (name "Net-(C17-Pad1)") (class "Default")
      (node (ref "C17") (pin "1") (pinfunction "1_1") (pintype "passive"))
      (node (ref "R6") (pin "2") (pinfunction "2_2") (pintype "passive"))
    )
    (net (code "43") (name "Net-(DA-0)") (class "Default")
      (node (ref "DA") (pin "1") (pinfunction "0_1") (pintype "passive"))
      (node (ref "DA2") (pin "2") (pinfunction "1_2") (pintype "passive"))
      (node (ref "R10") (pin "1") (pinfunction "1_1") (pintype "passive"))
    )
    (net (code "44") (name "Net-(DA-1)") (class "Default")
      (node (ref "DA") (pin "2") (pinfunction "1_2") (pintype "passive"))
      (node (ref "IC4") (pin "6") (pinfunction "DA_6") (pintype "passive"))
    )
    (net (code "45") (name "Net-(DB-0)") (class "Default")
      (node (ref "C35") (pin "1") (pinfunction "1_1") (pintype "passive"))
      (node (ref "DB") (pin "1") (pinfunction "0_1") (pintype "passive"))
      (node (ref "DB2") (pin "1") (pinfunction "0_1") (pintype "passive"))
    )
    (net (code "46") (name "Net-(DB-1)") (class "Default")
      (node (ref "DB") (pin "2") (pinfunction "1_2") (pintype "passive"))
      (node (ref "IC4") (pin "7") (pinfunction "DB_7") (pintype "passive"))
    )
    (net (code "47") (name "Net-(GR1-1)") (class "Default")
      (node (ref "GR1") (pin "2") (pinfunction "1_2") (pintype "passive"))
      (node (ref "GREEN1") (pin "2") (pinfunction "A_2") (pintype "passive"))
    )
    (net (code "48") (name "Net-(GR2-1)") (class "Default")
      (node (ref "GR2") (pin "2") (pinfunction "1_2") (pintype "passive"))
      (node (ref "GREEN2") (pin "2") (pinfunction "A_2") (pintype "passive"))
    )
    (net (code "49") (name "Net-(IC1-(PPG_INT)_P0.3)") (class "Default")
      (node (ref "IC1") (pin "38") (pinfunction "(PPG_INT)_P0.3_38") (pintype "passive"))
      (node (ref "R2") (pin "1") (pinfunction "1_1") (pintype "passive"))
    )
    (net (code "50") (name "Net-(IC1-AFE_GPIO1)") (class "Default")
      (node (ref "IC1") (pin "28") (pinfunction "AFE_GPIO1_28") (pintype "passive"))
      (node (ref "IC2") (pin "A2") (pinfunction "CB_A2") (pintype "passive"))
      (node (ref "R5") (pin "2") (pinfunction "2_2") (pintype "passive"))
    )
    (net (code "51") (name "Net-(IC1-LED2_DRV)") (class "Default")
      (node (ref "IC1") (pin "20") (pinfunction "LED2_DRV_20") (pintype "passive"))
      (node (ref "IC2") (pin "B1") (pinfunction "COM1_B1") (pintype "passive"))
    )
    (net (code "52") (name "Net-(IC1-LED3_DRV)") (class "Default")
      (node (ref "IC1") (pin "19") (pinfunction "LED3_DRV_19") (pintype "passive"))
      (node (ref "IC2") (pin "B3") (pinfunction "COM2_B3") (pintype "passive"))
    )
    (net (code "53") (name "Net-(IC1-PD2_CAT)") (class "Default")
      (node (ref "IC1") (pin "25") (pinfunction "PD2_IN_25") (pintype "passive"))
      (node (ref "IC1") (pin "26") (pinfunction "PD2_CAT_26") (pintype "passive"))
    )
    (net (code "54") (name "Net-(IC1-VCORE)") (class "Default")
      (node (ref "C9") (pin "2") (pinfunction "2_2") (pintype "passive"))
      (node (ref "IC1") (pin "5") (pinfunction "VCORE_5") (pintype "passive"))
    )
    (net (code "55") (name "Net-(IC3-BIN)") (class "Default")
      (node (ref "C33") (pin "1") (pinfunction "1_1") (pintype "passive"))
      (node (ref "C34") (pin "2") (pinfunction "2_2") (pintype "passive"))
      (node (ref "IC3") (pin "A3") (pinfunction "BIN_A3") (pintype "passive"))
      (node (ref "R10") (pin "2") (pinfunction "2_2") (pintype "passive"))
    )
    (net (code "56") (name "Net-(IC3-BIP)") (class "Default")
      (node (ref "C32") (pin "2") (pinfunction "2_2") (pintype "passive"))
      (node (ref "C33") (pin "2") (pinfunction "2_2") (pintype "passive"))
      (node (ref "IC3") (pin "A4") (pinfunction "BIP_A4") (pintype "passive"))
      (node (ref "R9") (pin "2") (pinfunction "2_2") (pintype "passive"))
    )
    (net (code "57") (name "Net-(IC3-CAPN)") (class "Default")
      (node (ref "C27") (pin "1") (pinfunction "1_1") (pintype "passive"))
      (node (ref "IC3") (pin "B5") (pinfunction "CAPN_B5") (pintype "passive"))
    )
    (net (code "58") (name "Net-(IC3-CAPP)") (class "Default")
      (node (ref "C27") (pin "2") (pinfunction "2_2") (pintype "passive"))
      (node (ref "IC3") (pin "B6") (pinfunction "CAPP_B6") (pintype "passive"))
    )
    (net (code "59") (name "Net-(IC3-CSB)") (class "Default")
      (node (ref "CS") (pin "1") (pinfunction "1_1") (pintype "passive"))
      (node (ref "IC3") (pin "E6") (pinfunction "CSB_E6") (pintype "passive"))
    )
    (net (code "60") (name "Net-(IC3-DRVN)") (class "Default")
      (node (ref "C35") (pin "2") (pinfunction "2_2") (pintype "passive"))
      (node (ref "IC3") (pin "A2") (pinfunction "DRVN_A2") (pintype "passive"))
    )
    (net (code "61") (name "Net-(IC3-DRVP)") (class "Default")
      (node (ref "C37") (pin "2") (pinfunction "2_2") (pintype "passive"))
      (node (ref "IC3") (pin "A1") (pinfunction "DRVP_A1") (pintype "passive"))
    )
    (net (code "62") (name "Net-(IC3-ECGN)") (class "Default")
      (node (ref "C28") (pin "1") (pinfunction "1_1") (pintype "passive"))
      (node (ref "C29") (pin "2") (pinfunction "2_2") (pintype "passive"))
      (node (ref "IC3") (pin "A6") (pinfunction "ECGN_A6") (pintype "passive"))
      (node (ref "R8") (pin "2") (pinfunction "2_2") (pintype "passive"))
    )
    (net (code "63") (name "Net-(IC3-ECGP)") (class "Default")
      (node (ref "C26") (pin "2") (pinfunction "2_2") (pintype "passive"))
      (node (ref "C28") (pin "2") (pinfunction "2_2") (pintype "passive"))
      (node (ref "IC3") (pin "A5") (pinfunction "ECGP_A5") (pintype "passive"))
      (node (ref "R7") (pin "2") (pinfunction "2_2") (pintype "passive"))
    )
    (net (code "64") (name "Net-(IC3-INT2B)") (class "Default")
      (node (ref "IC3") (pin "E2") (pinfunction "INT2B_E2") (pintype "passive"))
      (node (ref "INT2") (pin "1") (pinfunction "1_1") (pintype "passive"))
    )
    (net (code "65") (name "Net-(IC3-INTB)") (class "Default")
      (node (ref "IC3") (pin "D2") (pinfunction "INTB_D2") (pintype "passive"))
      (node (ref "INT") (pin "1") (pinfunction "1_1") (pintype "passive"))
    )
    (net (code "66") (name "Net-(IC3-SCLK)") (class "Default")
      (node (ref "IC3") (pin "E5") (pinfunction "SCLK_E5") (pintype "passive"))
      (node (ref "SCLK") (pin "1") (pinfunction "1_1") (pintype "passive"))
    )
    (net (code "67") (name "Net-(IC3-SDI)") (class "Default")
      (node (ref "IC3") (pin "E4") (pinfunction "SDI_E4") (pintype "passive"))
      (node (ref "MOSI") (pin "1") (pinfunction "1_1") (pintype "passive"))
    )
    (net (code "68") (name "Net-(IC3-SDO)") (class "Default")
      (node (ref "IC3") (pin "E3") (pinfunction "SDO_E3") (pintype "passive"))
      (node (ref "MISO") (pin "1") (pinfunction "1_1") (pintype "passive"))
    )
    (net (code "69") (name "Net-(IC4-A0)") (class "Default")
      (node (ref "A0") (pin "1") (pinfunction "1_1") (pintype "passive"))
      (node (ref "IC4") (pin "15") (pinfunction "A0_15") (pintype "passive"))
    )
    (net (code "70") (name "Net-(IC4-A1)") (class "Default")
      (node (ref "A1") (pin "1") (pinfunction "1_1") (pintype "passive"))
      (node (ref "IC4") (pin "14") (pinfunction "A1_14") (pintype "passive"))
    )
    (net (code "71") (name "Net-(IC4-EN)") (class "Default")
      (node (ref "C30") (pin "2") (pinfunction "2_2") (pintype "passive"))
      (node (ref "IC4") (pin "12") (pinfunction "VDD_12") (pintype "passive"))
      (node (ref "IC4") (pin "16") (pinfunction "EN_16") (pintype "passive"))
      (node (ref "MUX_EN") (pin "2") (pinfunction "1_2") (pintype "passive"))
    )
    (net (code "72") (name "Net-(IC4-VSS)") (class "Default")
      (node (ref "C31") (pin "2") (pinfunction "2_2") (pintype "passive"))
      (node (ref "IC4") (pin "1") (pinfunction "VSS_1") (pintype "passive"))
    )
    (net (code "73") (name "Net-(IR/RED-A)") (class "Default")
      (node (ref "IR/RED") (pin "3") (pinfunction "A_3") (pintype "passive"))
      (node (ref "RED/IR") (pin "2") (pinfunction "1_2") (pintype "passive"))
    )
    (net (code "74") (name "VDD") (class "Default")
      (node (ref "AC1") (pin "3") (pinfunction "IO_VDD_3") (pintype "passive"))
      (node (ref "AC1") (pin "7") (pinfunction "VDD_7") (pintype "passive"))
      (node (ref "C12") (pin "2") (pinfunction "2_2") (pintype "passive"))
      (node (ref "C13") (pin "2") (pinfunction "2_2") (pintype "passive"))
      (node (ref "C14") (pin "2") (pinfunction "2_2") (pintype "passive"))
      (node (ref "C20") (pin "2") (pinfunction "2_2") (pintype "passive"))
      (node (ref "C21") (pin "2") (pinfunction "2_2") (pintype "passive"))
      (node (ref "C22") (pin "2") (pinfunction "2_2") (pintype "passive"))
      (node (ref "C23") (pin "2") (pinfunction "2_2") (pintype "passive"))
      (node (ref "C24") (pin "2") (pinfunction "2_2") (pintype "passive"))
      (node (ref "C25") (pin "2") (pinfunction "2_2") (pintype "passive"))
      (node (ref "C5") (pin "2") (pinfunction "2_2") (pintype "passive"))
      (node (ref "C6") (pin "2") (pinfunction "2_2") (pintype "passive"))
      (node (ref "C7") (pin "2") (pinfunction "2_2") (pintype "passive"))
      (node (ref "IC1") (pin "22") (pinfunction "VDD_AFE_22") (pintype "passive"))
      (node (ref "IC1") (pin "6") (pinfunction "VDD_6") (pintype "passive"))
      (node (ref "IC2") (pin "C2") (pinfunction "VCC_C2") (pintype "passive"))
      (node (ref "IC3") (pin "D3") (pinfunction "OVDD_D3") (pintype "passive"))
      (node (ref "IC3") (pin "D6") (pinfunction "DVDD_D6") (pintype "passive"))
      (node (ref "IC3") (pin "E1") (pinfunction "AVDD_E1") (pintype "passive"))
      (node (ref "MUX_EN") (pin "1") (pinfunction "0_1") (pintype "passive"))
      (node (ref "R2") (pin "2") (pinfunction "2_2") (pintype "passive"))
      (node (ref "R3") (pin "2") (pinfunction "2_2") (pintype "passive"))
      (node (ref "R4") (pin "2") (pinfunction "2_2") (pintype "passive"))
      (node (ref "Y1") (pin "3") (pinfunction "VDD_3") (pintype "passive"))
    )
    (net (code "75") (name "VLED") (class "Default")
      (node (ref "C10") (pin "2") (pinfunction "2_2") (pintype "passive"))
      (node (ref "C11") (pin "2") (pinfunction "2_2") (pintype "passive"))
      (node (ref "C15") (pin "2") (pinfunction "2_2") (pintype "passive"))
      (node (ref "C16") (pin "2") (pinfunction "2_2") (pintype "passive"))
      (node (ref "C18") (pin "2") (pinfunction "2_2") (pintype "passive"))
      (node (ref "C19") (pin "2") (pinfunction "2_2") (pintype "passive"))
      (node (ref "C8") (pin "2") (pinfunction "2_2") (pintype "passive"))
      (node (ref "GR1") (pin "1") (pinfunction "0_1") (pintype "passive"))
      (node (ref "GR2") (pin "1") (pinfunction "0_1") (pintype "passive"))
      (node (ref "IC1") (pin "18") (pinfunction "VLED_18") (pintype "passive"))
      (node (ref "RED/IR") (pin "1") (pinfunction "0_1") (pintype "passive"))
    )
    (net (code "76") (name "unconnected-(AC1-INT2-Pad6)") (class "Default")
      (node (ref "AC1") (pin "6") (pinfunction "INT2_6") (pintype "passive+no_connect"))
    )
    (net (code "77") (name "unconnected-(GREEN1-A-Pad2)") (class "Default")
      (node (ref "GREEN1") (pin "2") (pinfunction "A_2") (pintype "passive"))
    )
    (net (code "78") (name "unconnected-(GREEN1-C-Pad1)") (class "Default")
      (node (ref "GREEN1") (pin "1") (pinfunction "C_1") (pintype "passive"))
    )
    (net (code "79") (name "unconnected-(GREEN2-A-Pad2)") (class "Default")
      (node (ref "GREEN2") (pin "2") (pinfunction "A_2") (pintype "passive"))
    )
    (net (code "80") (name "unconnected-(GREEN2-C-Pad1)") (class "Default")
      (node (ref "GREEN2") (pin "1") (pinfunction "C_1") (pintype "passive"))
    )
    (net (code "81") (name "unconnected-(IC1-32KOUT-Pad9)") (class "Default")
      (node (ref "IC1") (pin "9") (pinfunction "32KOUT_9") (pintype "passive+no_connect"))
    )
    (net (code "82") (name "unconnected-(IC1-N.C._1-Pad14)") (class "Default")
      (node (ref "IC1") (pin "14") (pinfunction "N.C._1_14") (pintype "passive+no_connect"))
    )
    (net (code "83") (name "unconnected-(IC1-N.C._2-Pad15)") (class "Default")
      (node (ref "IC1") (pin "15") (pinfunction "N.C._2_15") (pintype "passive+no_connect"))
    )
    (net (code "84") (name "unconnected-(IC1-N.C._3-Pad16)") (class "Default")
      (node (ref "IC1") (pin "16") (pinfunction "N.C._3_16") (pintype "passive+no_connect"))
    )
    (net (code "85") (name "unconnected-(IC1-N.C._4-Pad17)") (class "Default")
      (node (ref "IC1") (pin "17") (pinfunction "N.C._4_17") (pintype "passive+no_connect"))
    )
    (net (code "86") (name "unconnected-(IC1-N.C._5-Pad27)") (class "Default")
      (node (ref "IC1") (pin "27") (pinfunction "N.C._5_27") (pintype "passive+no_connect"))
    )
    (net (code "87") (name "unconnected-(IC1-N.C._6-Pad34)") (class "Default")
      (node (ref "IC1") (pin "34") (pinfunction "N.C._6_34") (pintype "passive+no_connect"))
    )
    (net (code "88") (name "unconnected-(IC1-PD1_IN-Pad1)") (class "Default")
      (node (ref "IC1") (pin "1") (pinfunction "PD1_IN_1") (pintype "passive+no_connect"))
    )
    (net (code "89") (name "unconnected-(IC3-AOUT-PadC2)") (class "Default")
      (node (ref "IC3") (pin "C2") (pinfunction "AOUT_C2") (pintype "passive+no_connect"))
    )
    (net (code "90") (name "unconnected-(IR/RED-NC-Pad1)") (class "Default")
      (node (ref "IR/RED") (pin "1") (pinfunction "NC_1") (pintype "passive+no_connect"))
    )
  )
)
